# WZ8048C070-V1_1-20230407.net
KiCad netlist of a schematic drawn in EAGLE
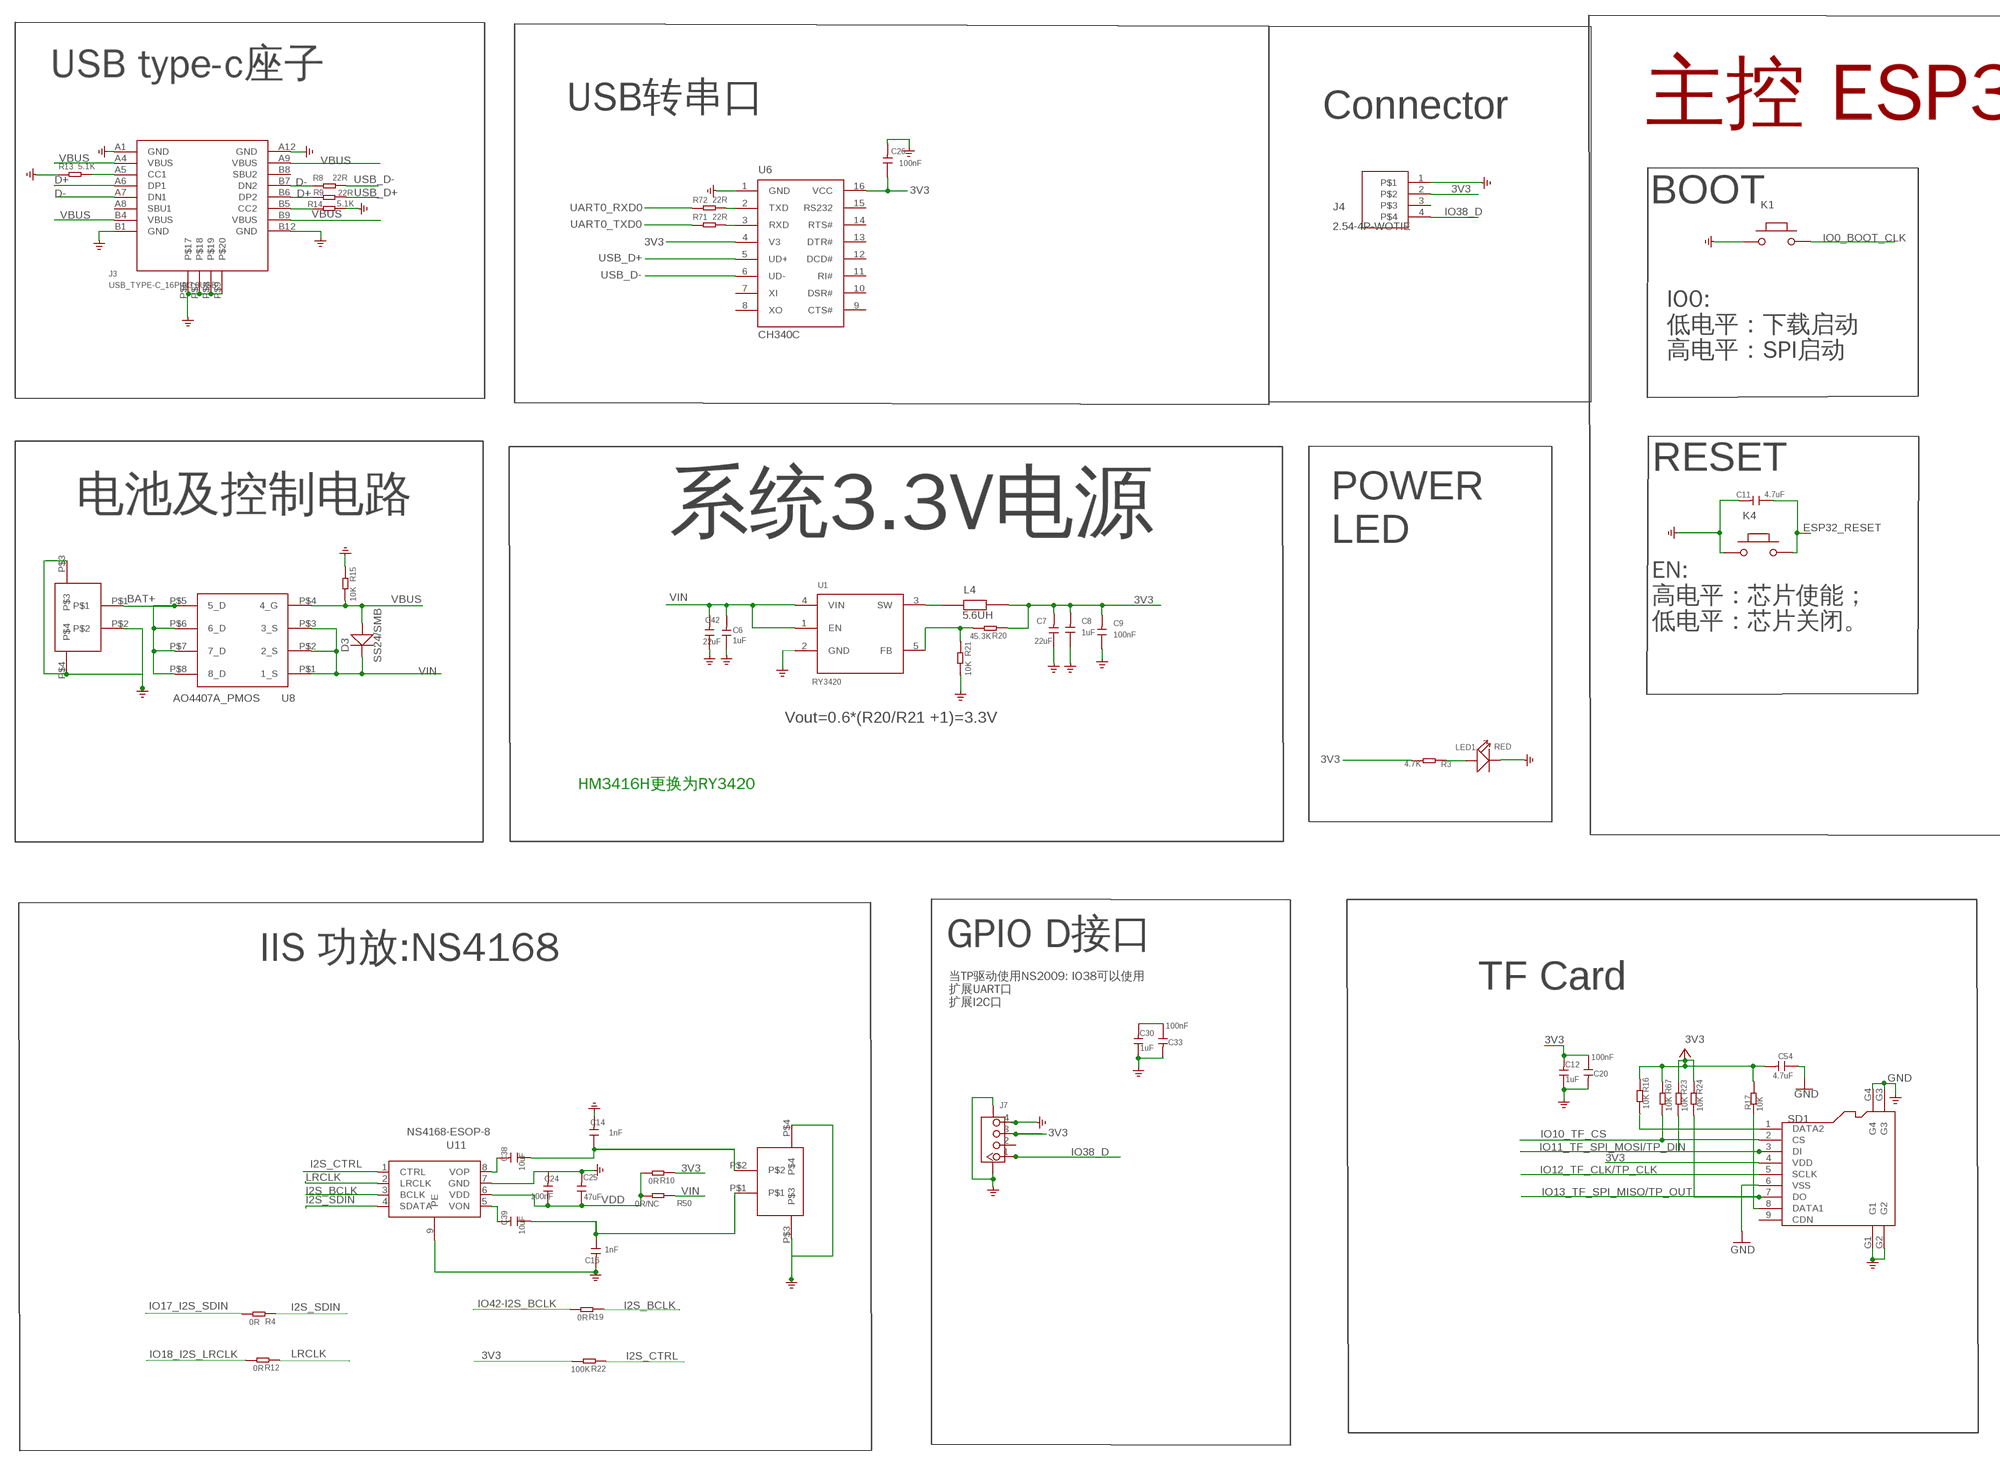
[diagram p0: schematic, sheet 1, part 1 of 2]
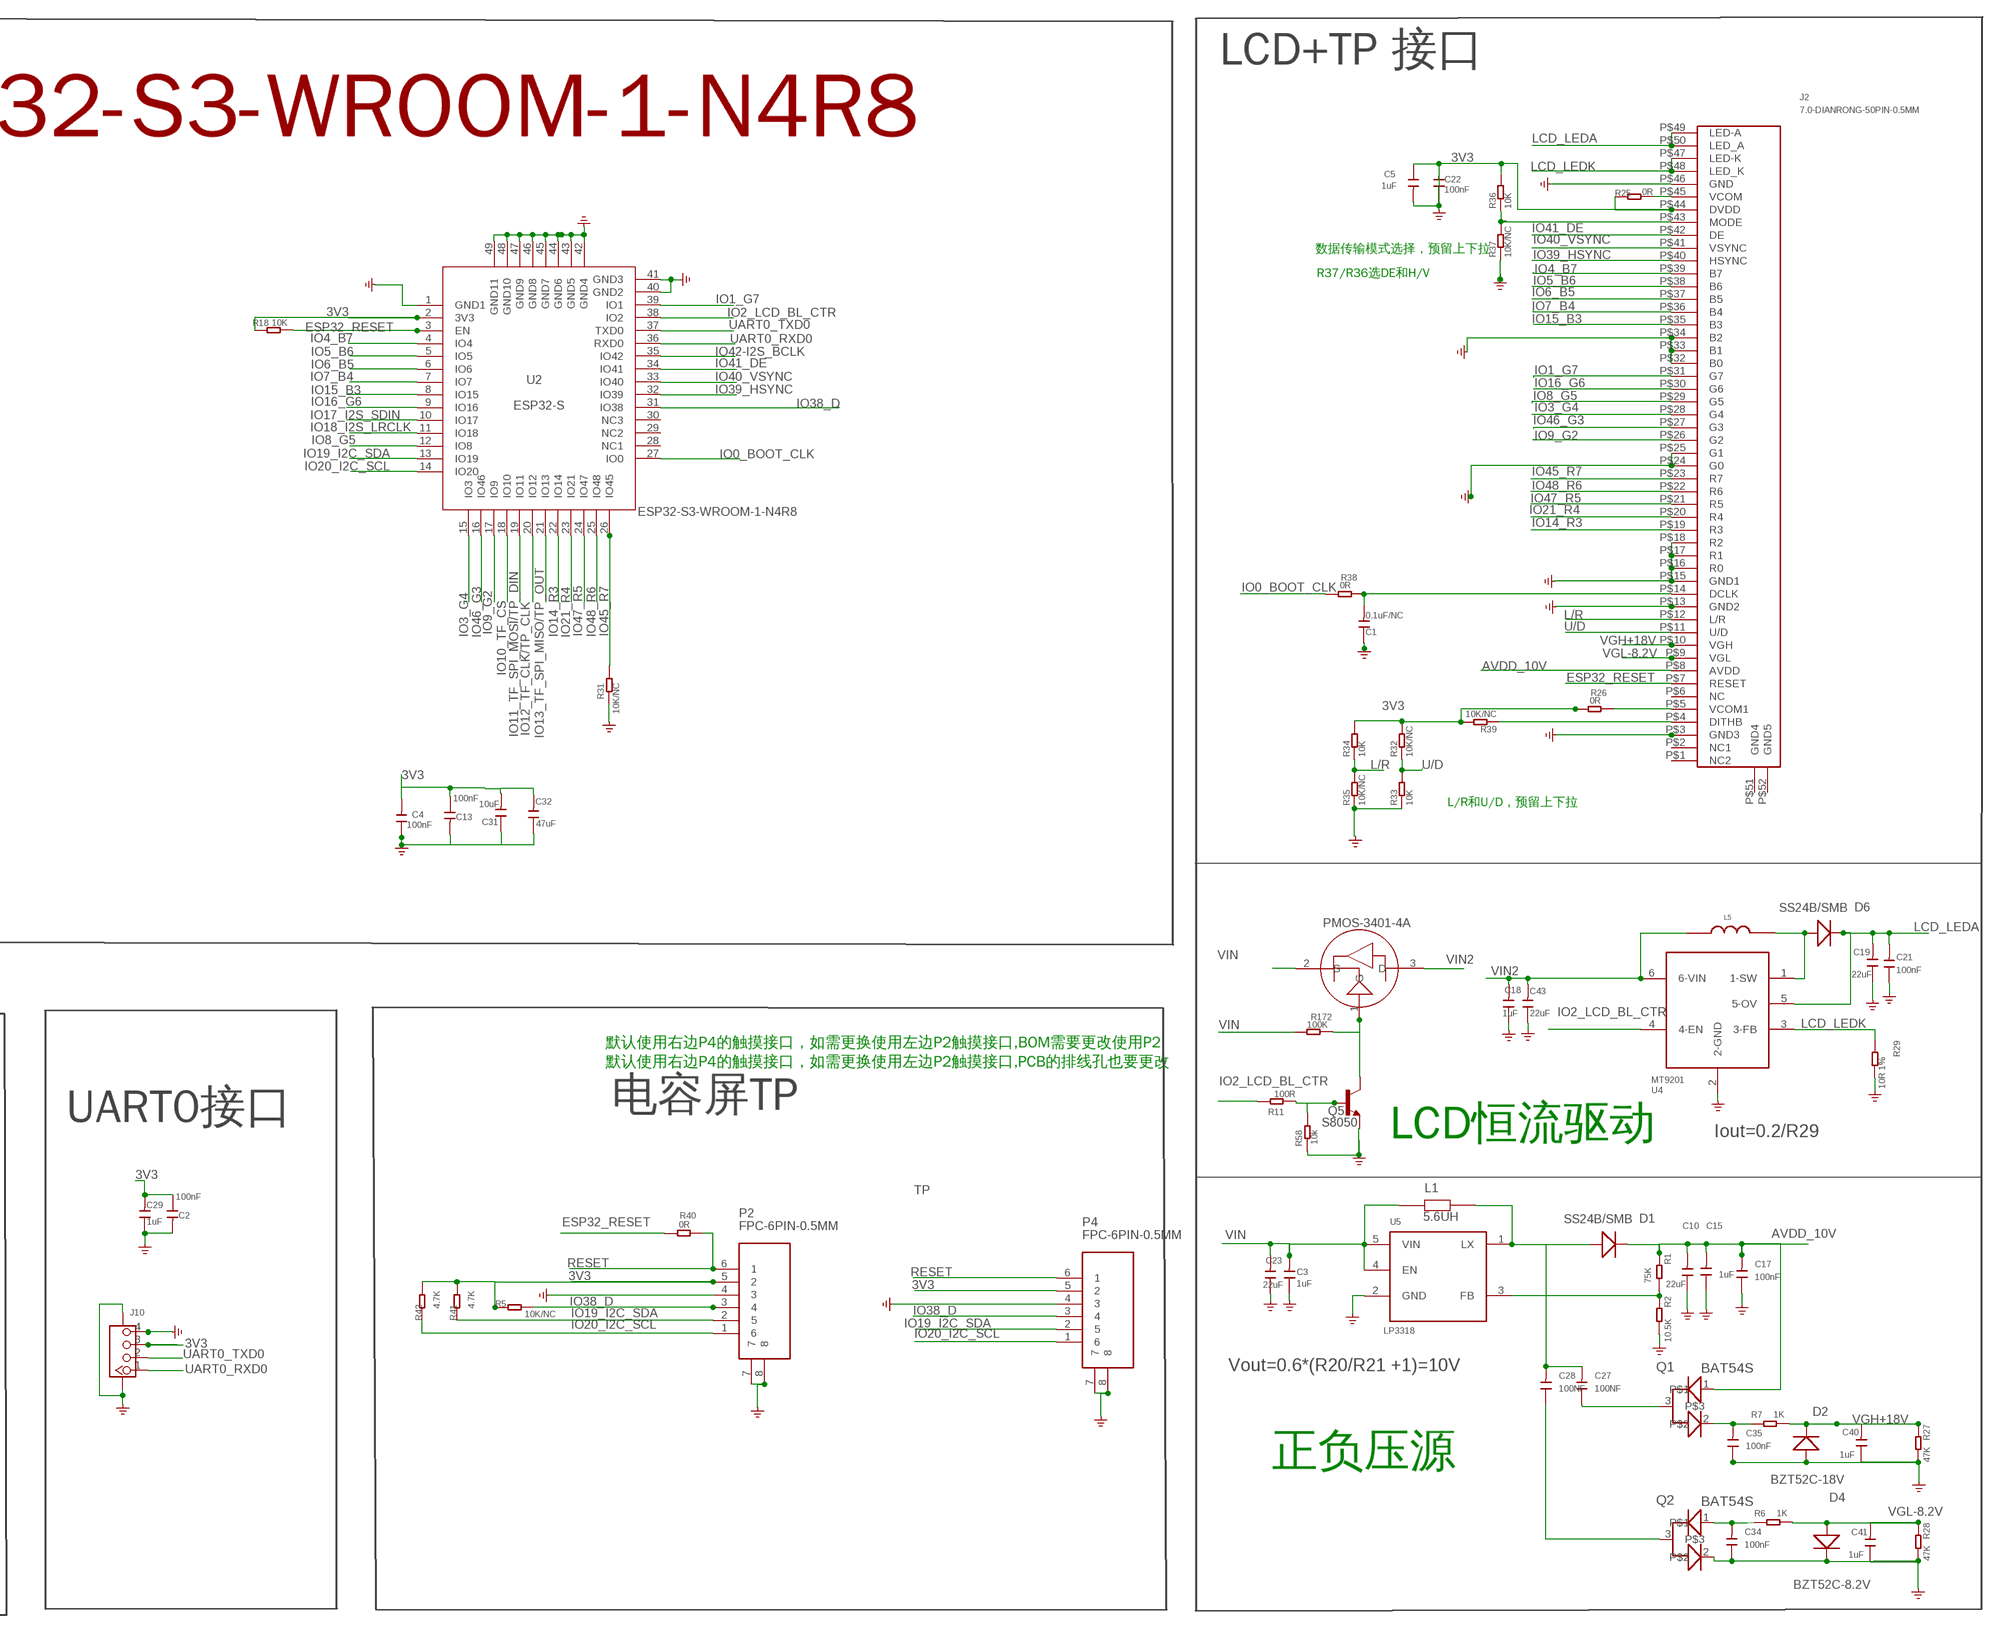
[diagram p1: schematic, sheet 1, part 2 of 2]

(export (version "E")
  (design (tool "Eeschema 10.0.6"))
  (components
    (comp (ref "C1")
      (value "0.1uF/NC")
      (footprint "eagle-import:DISCRETE_C0603")
      (libsource (lib "eagle-import") (part "DISCRETE_C-0603"))
    )
    (comp (ref "C2")
      (value "100nF")
      (footprint "eagle-import:C0603")
      (libsource (lib "eagle-import") (part "C-0603"))
    )
    (comp (ref "C3")
      (value "1uF")
      (footprint "eagle-import:0603")
      (libsource (lib "eagle-import") (part "C0603"))
    )
    (comp (ref "C4")
      (value "100nF")
      (footprint "eagle-import:C0603")
      (libsource (lib "eagle-import") (part "C-0603"))
    )
    (comp (ref "C5")
      (value "1uF")
      (footprint "eagle-import:C0603")
      (libsource (lib "eagle-import") (part "C-0603"))
    )
    (comp (ref "C6")
      (value "1uF")
      (footprint "eagle-import:0603")
      (libsource (lib "eagle-import") (part "C0603"))
    )
    (comp (ref "C7")
      (value "22uF")
      (footprint "eagle-import:0805")
      (libsource (lib "eagle-import") (part "C0805"))
    )
    (comp (ref "C8")
      (value "1uF")
      (footprint "eagle-import:0603")
      (libsource (lib "eagle-import") (part "C0603"))
    )
    (comp (ref "C9")
      (value "100nF")
      (footprint "eagle-import:0603")
      (libsource (lib "eagle-import") (part "C0603"))
    )
    (comp (ref "C10")
      (value "22uF")
      (footprint "eagle-import:0805")
      (libsource (lib "eagle-import") (part "C0805"))
    )
    (comp (ref "C11")
      (value "4.7uF")
      (footprint "eagle-import:0603")
      (libsource (lib "eagle-import") (part "C0603"))
    )
    (comp (ref "C12")
      (value "1uF")
      (footprint "eagle-import:DISCRETE_C0603")
      (libsource (lib "eagle-import") (part "A_xbj_DISCRETE_C-0603"))
    )
    (comp (ref "C13")
      (value "100nF")
      (footprint "eagle-import:C0603")
      (libsource (lib "eagle-import") (part "C-0603"))
    )
    (comp (ref "C14")
      (value "1nF")
      (footprint "eagle-import:C0603")
      (libsource (lib "eagle-import") (part "C-0603"))
    )
    (comp (ref "C15")
      (value "1uF")
      (footprint "eagle-import:0603")
      (libsource (lib "eagle-import") (part "C0603"))
    )
    (comp (ref "C16")
      (value "1nF")
      (footprint "eagle-import:C0603")
      (libsource (lib "eagle-import") (part "C-0603"))
    )
    (comp (ref "C17")
      (value "100nF")
      (footprint "eagle-import:0603")
      (libsource (lib "eagle-import") (part "C0603"))
    )
    (comp (ref "C18")
      (value "1uF")
      (footprint "eagle-import:0603")
      (libsource (lib "eagle-import") (part "C0603"))
    )
    (comp (ref "C19")
      (value "22uF")
      (footprint "eagle-import:0805")
      (libsource (lib "eagle-import") (part "C0805"))
    )
    (comp (ref "C20")
      (value "100nF")
      (footprint "eagle-import:C0603")
      (libsource (lib "eagle-import") (part "C-0603"))
    )
    (comp (ref "C21")
      (value "100nF")
      (footprint "eagle-import:0603")
      (libsource (lib "eagle-import") (part "C0603"))
    )
    (comp (ref "C22")
      (value "100nF")
      (footprint "eagle-import:C0603")
      (libsource (lib "eagle-import") (part "C-0603"))
    )
    (comp (ref "C23")
      (value "22uF")
      (footprint "eagle-import:0805")
      (libsource (lib "eagle-import") (part "C0805"))
    )
    (comp (ref "C24")
      (value "100nF")
      (footprint "eagle-import:C0603")
      (libsource (lib "eagle-import") (part "C-0603"))
    )
    (comp (ref "C25")
      (value "47uF")
      (footprint "eagle-import:0805")
      (libsource (lib "eagle-import") (part "C0805"))
    )
    (comp (ref "C26")
      (value "100nF")
      (footprint "eagle-import:0603")
      (libsource (lib "eagle-import") (part "C0603"))
    )
    (comp (ref "C27")
      (value "100NF")
      (footprint "eagle-import:0603")
      (libsource (lib "eagle-import") (part "C0603"))
    )
    (comp (ref "C28")
      (value "100NF")
      (footprint "eagle-import:0603")
      (libsource (lib "eagle-import") (part "C0603"))
    )
    (comp (ref "C29")
      (value "1uF")
      (footprint "eagle-import:DISCRETE_C0603")
      (libsource (lib "eagle-import") (part "A_xbj_DISCRETE_C-0603"))
    )
    (comp (ref "C30")
      (value "1uF")
      (footprint "eagle-import:DISCRETE_C0603")
      (libsource (lib "eagle-import") (part "A_xbj_DISCRETE_C-0603"))
    )
    (comp (ref "C31")
      (value "10uF")
      (footprint "eagle-import:DISCRETE_C0603")
      (libsource (lib "eagle-import") (part "DISCRETE_C-0603"))
    )
    (comp (ref "C32")
      (value "47uF")
      (footprint "eagle-import:0805")
      (libsource (lib "eagle-import") (part "C0805"))
    )
    (comp (ref "C33")
      (value "100nF")
      (footprint "eagle-import:C0603")
      (libsource (lib "eagle-import") (part "C-0603"))
    )
    (comp (ref "C34")
      (value "100nF")
      (footprint "eagle-import:0603")
      (libsource (lib "eagle-import") (part "C0603"))
    )
    (comp (ref "C35")
      (value "100nF")
      (footprint "eagle-import:0603")
      (libsource (lib "eagle-import") (part "C0603"))
    )
    (comp (ref "C38")
      (value "10uF")
      (footprint "eagle-import:C0603")
      (libsource (lib "eagle-import") (part "C-0603"))
    )
    (comp (ref "C39")
      (value "10uF")
      (footprint "eagle-import:C0603")
      (libsource (lib "eagle-import") (part "C-0603"))
    )
    (comp (ref "C40")
      (value "1uF")
      (footprint "eagle-import:0805")
      (libsource (lib "eagle-import") (part "C0805"))
    )
    (comp (ref "C41")
      (value "1uF")
      (footprint "eagle-import:0805")
      (libsource (lib "eagle-import") (part "C0805"))
    )
    (comp (ref "C42")
      (value "22uF")
      (footprint "eagle-import:0805")
      (libsource (lib "eagle-import") (part "C0805"))
    )
    (comp (ref "C43")
      (value "22uF")
      (footprint "eagle-import:0805")
      (libsource (lib "eagle-import") (part "C0805"))
    )
    (comp (ref "C54")
      (value "4.7uF")
      (footprint "eagle-import:DISCRETE_C0603")
      (libsource (lib "eagle-import") (part "DISCRETE_C-0603"))
    )
    (comp (ref "D1")
      (value "SS24B/SMB")
      (footprint "eagle-import:214AB")
      (libsource (lib "eagle-import") (part "214ABDO-214AB"))
    )
    (comp (ref "D2")
      (value "BZT52C-18V")
      (footprint "eagle-import:DISCRETE_SOD123")
      (libsource (lib "eagle-import") (part "DISCRETE_D1206"))
    )
    (comp (ref "D3")
      (value "SS24/SMB")
      (footprint "eagle-import:214AB")
      (libsource (lib "eagle-import") (part "214ABDO-214AB"))
    )
    (comp (ref "D4")
      (value "BZT52C-8.2V")
      (footprint "eagle-import:DISCRETE_SOD123")
      (libsource (lib "eagle-import") (part "DISCRETE_D1206"))
    )
    (comp (ref "D6")
      (value "SS24B/SMB")
      (footprint "eagle-import:214AB")
      (libsource (lib "eagle-import") (part "214ABDO-214AB"))
    )
    (comp (ref "J1")
      (value "PH2.0WT-2PIN")
      (footprint "eagle-import:PH2.0WT-2PIN")
      (libsource (lib "eagle-import") (part "PH2.0WT-2PIN"))
    )
    (comp (ref "J2")
      (value "7.0-DIANRONG-50PIN-0.5MM")
      (footprint "eagle-import:7.0-DAINRONG-50PIN-0.5MM")
      (libsource (lib "eagle-import") (part "7.0-DIANRONG-50PIN-0.5MM"))
    )
    (comp (ref "J3")
      (value "USB_TYPE-C_16PIN3.0USB")
      (footprint "eagle-import:KEVIN_3.0TYPEC-SMD")
      (libsource (lib "eagle-import") (part "USB_TYPE-C_16PIN3.0USB"))
    )
    (comp (ref "J4")
      (value "2.54-4P-WOTIE")
      (footprint "eagle-import:2.54-4P-WOTIE")
      (libsource (lib "eagle-import") (part "2.54-4P-WOTIE"))
    )
    (comp (ref "J5")
      (value "PH2.0WT-2PIN")
      (footprint "eagle-import:PH2.0WT-2PIN")
      (libsource (lib "eagle-import") (part "PH2.0WT-2PIN"))
    )
    (comp (ref "J7")
      (value "CONNECTOR_TWIG-4P-2.0-SMD-FEMALE-REINFORCE90D")
      (footprint "eagle-import:CONNECTOR_4P-SMD-2.0-90D")
      (libsource (lib "eagle-import") (part "CONNECTOR_TWIG-4P-2.0-SMD-FEMALE-REINFORCE90D"))
    )
    (comp (ref "J10")
      (value "CONNECTOR_TWIG-4P-2.0-SMD-FEMALE-REINFORCE90D")
      (footprint "eagle-import:CONNECTOR_4P-SMD-2.0-90D")
      (libsource (lib "eagle-import") (part "CONNECTOR_TWIG-4P-2.0-SMD-FEMALE-REINFORCE90D"))
    )
    (comp (ref "K1")
      (value "BUTTON")
      (footprint "eagle-import:157SW")
      (libsource (lib "eagle-import") (part "PB157"))
    )
    (comp (ref "K4")
      (value "BUTTON")
      (footprint "eagle-import:157SW")
      (libsource (lib "eagle-import") (part "PB157"))
    )
    (comp (ref "L1")
      (value "5.6UH")
      (footprint "eagle-import:CD54")
      (libsource (lib "eagle-import") (part "CROWPI2-MB-V1.4-20211012_CMP201209UD1R0MT"))
    )
    (comp (ref "L4")
      (value "5.6UH")
      (footprint "eagle-import:CD54")
      (libsource (lib "eagle-import") (part "CROWPI2-MB-V1.4-20211012_CMP201209UD1R0MT"))
    )
    (comp (ref "L5")
      (value "CD32_6.8uH")
      (footprint "eagle-import:CD32")
      (libsource (lib "eagle-import") (part "CD32_950MA"))
    )
    (comp (ref "LED1")
      (value "RED")
      (footprint "eagle-import:DISCRETE_LED-0603")
      (libsource (lib "eagle-import") (part "DISCRETE_LED0603"))
    )
    (comp (ref "P2")
      (value "FPC-6PIN-0.5MM")
      (footprint "eagle-import:FPC-6PIN-0.5MM")
      (libsource (lib "eagle-import") (part "FPC-6PIN-0.5MM"))
    )
    (comp (ref "P4")
      (value "FPC-6PIN-0.5MM")
      (footprint "eagle-import:FPC-6PIN-0.5MM")
      (libsource (lib "eagle-import") (part "FPC-6PIN-0.5MM"))
    )
    (comp (ref "Q1")
      (value "BAT54S")
      (footprint "eagle-import:SOT23-3")
      (libsource (lib "eagle-import") (part "BAT54S"))
    )
    (comp (ref "Q2")
      (value "BAT54S")
      (footprint "eagle-import:SOT23-3")
      (libsource (lib "eagle-import") (part "BAT54S"))
    )
    (comp (ref "Q5")
      (value "S8050")
      (footprint "eagle-import:SPARKFUN_SOT23")
      (libsource (lib "eagle-import") (part "SPARKFUN_TRANSISTOR_NPNSOT23"))
    )
    (comp (ref "Q30")
      (value "PMOS-3401-4A")
      (footprint "eagle-import:SOT-23")
      (libsource (lib "eagle-import") (part "P-MOS-SOT23"))
    )
    (comp (ref "R1")
      (value "75K")
      (footprint "eagle-import:DISCRETE_R0603")
      (libsource (lib "eagle-import") (part "Crowtail-_LED-V2.0-20190615-01_DISCRETE_R-0603"))
    )
    (comp (ref "R2")
      (value "10.5K")
      (footprint "eagle-import:DISCRETE_R0603")
      (libsource (lib "eagle-import") (part "Crowtail-_LED-V2.0-20190615-01_DISCRETE_R-0603"))
    )
    (comp (ref "R3")
      (value "4.7K")
      (footprint "eagle-import:DISCRETE_R0603")
      (libsource (lib "eagle-import") (part "Crowtail-_LED-V2.0-20190615-01_DISCRETE_R-0603"))
    )
    (comp (ref "R4")
      (value "0R")
      (footprint "eagle-import:DISCRETE_R0603")
      (libsource (lib "eagle-import") (part "Crowtail-_LED-V2.0-20190615-01_DISCRETE_R-0603"))
    )
    (comp (ref "R5")
      (value "10K/NC")
      (footprint "eagle-import:DISCRETE_R0603")
      (libsource (lib "eagle-import") (part "Crowtail-_LED-V2.0-20190615-01_DISCRETE_R-0603"))
    )
    (comp (ref "R6")
      (value "1K")
      (footprint "eagle-import:DISCRETE_R0603")
      (libsource (lib "eagle-import") (part "Crowtail-_LED-V2.0-20190615-01_DISCRETE_R-0603"))
    )
    (comp (ref "R7")
      (value "1K")
      (footprint "eagle-import:DISCRETE_R0603")
      (libsource (lib "eagle-import") (part "Crowtail-_LED-V2.0-20190615-01_DISCRETE_R-0603"))
    )
    (comp (ref "R8")
      (value "22R")
      (footprint "eagle-import:DISCRETE_R0603")
      (libsource (lib "eagle-import") (part "Crowtail-_LED-V2.0-20190615-01_DISCRETE_R-0603"))
    )
    (comp (ref "R9")
      (value "22R")
      (footprint "eagle-import:DISCRETE_R0603")
      (libsource (lib "eagle-import") (part "Crowtail-_LED-V2.0-20190615-01_DISCRETE_R-0603"))
    )
    (comp (ref "R10")
      (value "0R")
      (footprint "eagle-import:DISCRETE_R0603")
      (libsource (lib "eagle-import") (part "Crowtail-_LED-V2.0-20190615-01_DISCRETE_R-0603"))
    )
    (comp (ref "R11")
      (value "100R")
      (footprint "eagle-import:R0603")
      (libsource (lib "eagle-import") (part "R0603"))
    )
    (comp (ref "R12")
      (value "0R")
      (footprint "eagle-import:DISCRETE_R0603")
      (libsource (lib "eagle-import") (part "Crowtail-_LED-V2.0-20190615-01_DISCRETE_R-0603"))
    )
    (comp (ref "R13")
      (value "5.1K")
      (footprint "eagle-import:DISCRETE_R0603")
      (libsource (lib "eagle-import") (part "Crowtail-_LED-V2.0-20190615-01_DISCRETE_R-0603"))
    )
    (comp (ref "R14")
      (value "5.1K")
      (footprint "eagle-import:DISCRETE_R0603")
      (libsource (lib "eagle-import") (part "Crowtail-_LED-V2.0-20190615-01_DISCRETE_R-0603"))
    )
    (comp (ref "R15")
      (value "10K")
      (footprint "eagle-import:DISCRETE_R0603")
      (libsource (lib "eagle-import") (part "Crowtail-_LED-V2.0-20190615-01_DISCRETE_R-0603"))
    )
    (comp (ref "R16")
      (value "10K")
      (footprint "eagle-import:DISCRETE_R0603")
      (libsource (lib "eagle-import") (part "Crowtail-_LED-V2.0-20190615-01_DISCRETE_R-0603"))
    )
    (comp (ref "R17")
      (value "10K")
      (footprint "eagle-import:DISCRETE_R0603")
      (libsource (lib "eagle-import") (part "Crowtail-_LED-V2.0-20190615-01_DISCRETE_R-0603"))
    )
    (comp (ref "R18")
      (value "10K")
      (footprint "eagle-import:DISCRETE_R0603")
      (libsource (lib "eagle-import") (part "Crowtail-_LED-V2.0-20190615-01_DISCRETE_R-0603"))
    )
    (comp (ref "R19")
      (value "0R")
      (footprint "eagle-import:DISCRETE_R0603")
      (libsource (lib "eagle-import") (part "Crowtail-_LED-V2.0-20190615-01_DISCRETE_R-0603"))
    )
    (comp (ref "R20")
      (value "45.3K")
      (footprint "eagle-import:DISCRETE_R0603")
      (libsource (lib "eagle-import") (part "Crowtail-_LED-V2.0-20190615-01_DISCRETE_R-0603"))
    )
    (comp (ref "R21")
      (value "10K")
      (footprint "eagle-import:DISCRETE_R0603")
      (libsource (lib "eagle-import") (part "Crowtail-_LED-V2.0-20190615-01_DISCRETE_R-0603"))
    )
    (comp (ref "R22")
      (value "100K")
      (footprint "eagle-import:DISCRETE_R0603")
      (libsource (lib "eagle-import") (part "Crowtail-_LED-V2.0-20190615-01_DISCRETE_R-0603"))
    )
    (comp (ref "R23")
      (value "10K")
      (footprint "eagle-import:DISCRETE_R0603")
      (libsource (lib "eagle-import") (part "Crowtail-_LED-V2.0-20190615-01_DISCRETE_R-0603"))
    )
    (comp (ref "R24")
      (value "10K")
      (footprint "eagle-import:DISCRETE_R0603")
      (libsource (lib "eagle-import") (part "Crowtail-_LED-V2.0-20190615-01_DISCRETE_R-0603"))
    )
    (comp (ref "R25")
      (value "0R")
      (footprint "eagle-import:DISCRETE_R0603")
      (libsource (lib "eagle-import") (part "Crowtail-_LED-V2.0-20190615-01_DISCRETE_R-0603"))
    )
    (comp (ref "R26")
      (value "0R")
      (footprint "eagle-import:R0603")
      (libsource (lib "eagle-import") (part "R-0603"))
    )
    (comp (ref "R27")
      (value "47K")
      (footprint "eagle-import:DISCRETE_R0603")
      (libsource (lib "eagle-import") (part "Crowtail-_LED-V2.0-20190615-01_DISCRETE_R-0603"))
    )
    (comp (ref "R28")
      (value "47K")
      (footprint "eagle-import:DISCRETE_R0603")
      (libsource (lib "eagle-import") (part "Crowtail-_LED-V2.0-20190615-01_DISCRETE_R-0603"))
    )
    (comp (ref "R29")
      (value "10R 1%")
      (footprint "eagle-import:DISCRETE_R0603")
      (libsource (lib "eagle-import") (part "Crowtail-_LED-V2.0-20190615-01_DISCRETE_R-0603"))
    )
    (comp (ref "R31")
      (value "10K/NC")
      (footprint "eagle-import:R0603")
      (libsource (lib "eagle-import") (part "R0603"))
    )
    (comp (ref "R32")
      (value "10K/NC")
      (footprint "eagle-import:DISCRETE_R0603")
      (libsource (lib "eagle-import") (part "DISCRETE_R-0603"))
    )
    (comp (ref "R33")
      (value "10K")
      (footprint "eagle-import:DISCRETE_R0603")
      (libsource (lib "eagle-import") (part "DISCRETE_R-0603"))
    )
    (comp (ref "R34")
      (value "10K")
      (footprint "eagle-import:DISCRETE_R0603")
      (libsource (lib "eagle-import") (part "DISCRETE_R-0603"))
    )
    (comp (ref "R35")
      (value "10K/NC")
      (footprint "eagle-import:DISCRETE_R0603")
      (libsource (lib "eagle-import") (part "DISCRETE_R-0603"))
    )
    (comp (ref "R36")
      (value "10K")
      (footprint "eagle-import:DISCRETE_R0603")
      (libsource (lib "eagle-import") (part "DISCRETE_R-0603"))
    )
    (comp (ref "R37")
      (value "10K/NC")
      (footprint "eagle-import:DISCRETE_R0603")
      (libsource (lib "eagle-import") (part "DISCRETE_R-0603"))
    )
    (comp (ref "R38")
      (value "0R")
      (footprint "eagle-import:R0603")
      (libsource (lib "eagle-import") (part "R-0603"))
    )
    (comp (ref "R39")
      (value "10K/NC")
      (footprint "eagle-import:DISCRETE_R0603")
      (libsource (lib "eagle-import") (part "DISCRETE_R-0603"))
    )
    (comp (ref "R40")
      (value "0R")
      (footprint "eagle-import:R0603")
      (libsource (lib "eagle-import") (part "R-0603"))
    )
    (comp (ref "R41")
      (value "4.7K")
      (footprint "eagle-import:DISCRETE_R0603")
      (libsource (lib "eagle-import") (part "Crowtail-_LED-V2.0-20190615-01_DISCRETE_R-0603"))
    )
    (comp (ref "R42")
      (value "4.7K")
      (footprint "eagle-import:DISCRETE_R0603")
      (libsource (lib "eagle-import") (part "Crowtail-_LED-V2.0-20190615-01_DISCRETE_R-0603"))
    )
    (comp (ref "R50")
      (value "0R/NC")
      (footprint "eagle-import:DISCRETE_R0603")
      (libsource (lib "eagle-import") (part "Crowtail-_LED-V2.0-20190615-01_DISCRETE_R-0603"))
    )
    (comp (ref "R58")
      (value "10k")
      (footprint "eagle-import:R0603")
      (libsource (lib "eagle-import") (part "R0603"))
    )
    (comp (ref "R67")
      (value "10K")
      (footprint "eagle-import:DISCRETE_R0603")
      (libsource (lib "eagle-import") (part "Crowtail-_LED-V2.0-20190615-01_DISCRETE_R-0603"))
    )
    (comp (ref "R71")
      (value "22R")
      (footprint "eagle-import:DISCRETE_R0603")
      (libsource (lib "eagle-import") (part "Crowtail-_LED-V2.0-20190615-01_DISCRETE_R-0603"))
    )
    (comp (ref "R72")
      (value "22R")
      (footprint "eagle-import:DISCRETE_R0603")
      (libsource (lib "eagle-import") (part "Crowtail-_LED-V2.0-20190615-01_DISCRETE_R-0603"))
    )
    (comp (ref "R172")
      (value "100K")
      (footprint "eagle-import:R0603")
      (libsource (lib "eagle-import") (part "R-0603"))
    )
    (comp (ref "SD1")
      (value "HOLDER-MICROSD-9P")
      (footprint "eagle-import:9P-SMD-W_-RING")
      (libsource (lib "eagle-import") (part "HOLDER-MICROSD-9P"))
    )
    (comp (ref "U1")
      (value "RY3420")
      (footprint "eagle-import:A_XBJ_SOT23-5")
      (libsource (lib "eagle-import") (part "A_XBJ_HM3420B"))
    )
    (comp (ref "U2")
      (value "ESP32-S")
      (footprint "eagle-import:ESP32-S3")
      (fields (field (name "U2") "ESP32-S3-WROOM-1-N4R8"))
      (libsource (lib "eagle-import") (part "ESP32-S"))
    )
    (comp (ref "U4")
      (value "MT9201")
      (footprint "eagle-import:SOT23-6")
      (libsource (lib "eagle-import") (part "MT9201"))
    )
    (comp (ref "U5")
      (value "LP3318")
      (footprint "eagle-import:LP3318_SOT23-5")
      (libsource (lib "eagle-import") (part "LP3318"))
    )
    (comp (ref "U6")
      (value "CH340C")
      (footprint "eagle-import:SOP-16")
      (libsource (lib "eagle-import") (part "CH340G"))
    )
    (comp (ref "U8")
      (value "AO4407A_PMOS")
      (footprint "eagle-import:SOP8")
      (libsource (lib "eagle-import") (part "T_PMOS_AO4407A_SOP8"))
    )
    (comp (ref "U11")
      (value "NS4168-ESOP-8")
      (footprint "eagle-import:NS4168-ESOP-8")
      (libsource (lib "eagle-import") (part "NS4168-ESOP-8"))
    )
  )
  (nets
    (net (code "1") (name "+3V3") (class "Default")
      (node (ref "C12") (pin "2") (pinfunction "2_2") (pintype "passive"))
      (node (ref "C13") (pin "1") (pinfunction "1_1") (pintype "passive"))
      (node (ref "C2") (pin "1") (pinfunction "1_1") (pintype "passive"))
      (node (ref "C20") (pin "1") (pinfunction "1_1") (pintype "passive"))
      (node (ref "C22") (pin "2") (pinfunction "2_2") (pintype "passive"))
      (node (ref "C26") (pin "1") (pinfunction "1_1") (pintype "passive"))
      (node (ref "C29") (pin "2") (pinfunction "2_2") (pintype "passive"))
      (node (ref "C30") (pin "2") (pinfunction "2_2") (pintype "passive"))
      (node (ref "C31") (pin "2") (pinfunction "2_2") (pintype "passive"))
      (node (ref "C32") (pin "2") (pinfunction "2_2") (pintype "passive"))
      (node (ref "C33") (pin "1") (pinfunction "1_1") (pintype "passive"))
      (node (ref "C4") (pin "2") (pinfunction "2_2") (pintype "passive"))
      (node (ref "C5") (pin "1") (pinfunction "1_1") (pintype "passive"))
      (node (ref "C54") (pin "2") (pinfunction "2_2") (pintype "passive"))
      (node (ref "C7") (pin "2") (pinfunction "2_2") (pintype "passive"))
      (node (ref "C8") (pin "2") (pinfunction "2_2") (pintype "passive"))
      (node (ref "C9") (pin "2") (pinfunction "2_2") (pintype "passive"))
      (node (ref "J10") (pin "3") (pinfunction "3_3") (pintype "bidirectional"))
      (node (ref "J2") (pin "P$44") (pinfunction "DVDD_P$44") (pintype "bidirectional"))
      (node (ref "J4") (pin "2") (pinfunction "P$2_2") (pintype "bidirectional"))
      (node (ref "J7") (pin "3") (pinfunction "3_3") (pintype "bidirectional"))
      (node (ref "L4") (pin "2") (pinfunction "2_2") (pintype "bidirectional"))
      (node (ref "P2") (pin "5") (pinfunction "2_5") (pintype "bidirectional"))
      (node (ref "P4") (pin "5") (pinfunction "2_5") (pintype "bidirectional"))
      (node (ref "R10") (pin "1") (pinfunction "1_1") (pintype "passive"))
      (node (ref "R16") (pin "1") (pinfunction "1_1") (pintype "passive"))
      (node (ref "R17") (pin "1") (pinfunction "1_1") (pintype "passive"))
      (node (ref "R18") (pin "1") (pinfunction "1_1") (pintype "passive"))
      (node (ref "R20") (pin "1") (pinfunction "1_1") (pintype "passive"))
      (node (ref "R22") (pin "2") (pinfunction "2_2") (pintype "passive"))
      (node (ref "R23") (pin "1") (pinfunction "1_1") (pintype "passive"))
      (node (ref "R24") (pin "1") (pinfunction "1_1") (pintype "passive"))
      (node (ref "R25") (pin "1") (pinfunction "1_1") (pintype "passive"))
      (node (ref "R26") (pin "1") (pinfunction "1_1") (pintype "passive"))
      (node (ref "R3") (pin "2") (pinfunction "2_2") (pintype "passive"))
      (node (ref "R32") (pin "2") (pinfunction "2_2") (pintype "passive"))
      (node (ref "R34") (pin "2") (pinfunction "2_2") (pintype "passive"))
      (node (ref "R36") (pin "2") (pinfunction "2_2") (pintype "passive"))
      (node (ref "R39") (pin "2") (pinfunction "2_2") (pintype "passive"))
      (node (ref "R41") (pin "2") (pinfunction "2_2") (pintype "passive"))
      (node (ref "R42") (pin "2") (pinfunction "2_2") (pintype "passive"))
      (node (ref "R5") (pin "1") (pinfunction "1_1") (pintype "passive"))
      (node (ref "R67") (pin "1") (pinfunction "1_1") (pintype "passive"))
      (node (ref "SD1") (pin "4") (pinfunction "VDD_4") (pintype "bidirectional"))
      (node (ref "U2") (pin "2") (pinfunction "3V3_2") (pintype "bidirectional"))
      (node (ref "U6") (pin "16") (pinfunction "VCC_16") (pintype "bidirectional"))
      (node (ref "U6") (pin "4") (pinfunction "V3_4") (pintype "bidirectional"))
    )
    (net (code "2") (name "/AVDD_10V") (class "Default")
      (node (ref "C10") (pin "2") (pinfunction "2_2") (pintype "passive"))
      (node (ref "C15") (pin "2") (pinfunction "2_2") (pintype "passive"))
      (node (ref "C17") (pin "2") (pinfunction "2_2") (pintype "passive"))
      (node (ref "D1") (pin "2") (pinfunction "-_2") (pintype "passive"))
      (node (ref "J2") (pin "P$8") (pinfunction "AVDD_P$8") (pintype "bidirectional"))
      (node (ref "Q1") (pin "1") (pinfunction "P$1_1") (pintype "bidirectional"))
      (node (ref "R1") (pin "1") (pinfunction "1_1") (pintype "passive"))
    )
    (net (code "3") (name "/BAT+") (class "Default")
      (node (ref "J1") (pin "P$1") (pinfunction "P$1_P$1") (pintype "bidirectional"))
      (node (ref "U8") (pin "P$5") (pinfunction "5_D_P$5") (pintype "bidirectional"))
      (node (ref "U8") (pin "P$6") (pinfunction "6_D_P$6") (pintype "bidirectional"))
      (node (ref "U8") (pin "P$7") (pinfunction "7_D_P$7") (pintype "bidirectional"))
      (node (ref "U8") (pin "P$8") (pinfunction "8_D_P$8") (pintype "bidirectional"))
    )
    (net (code "4") (name "/D+") (class "Default")
      (node (ref "J3") (pin "A6") (pinfunction "DP1_A6") (pintype "bidirectional"))
      (node (ref "J3") (pin "B6") (pinfunction "DP2_B6") (pintype "bidirectional"))
      (node (ref "R9") (pin "1") (pinfunction "1_1") (pintype "passive"))
    )
    (net (code "5") (name "/D-") (class "Default")
      (node (ref "J3") (pin "A7") (pinfunction "DN1_A7") (pintype "bidirectional"))
      (node (ref "J3") (pin "B7") (pinfunction "DN2_B7") (pintype "bidirectional"))
      (node (ref "R8") (pin "1") (pinfunction "1_1") (pintype "passive"))
    )
    (net (code "6") (name "/ESP32_RESET") (class "Default")
      (node (ref "C11") (pin "1") (pinfunction "1_1") (pintype "passive"))
      (node (ref "J2") (pin "P$7") (pinfunction "RESET_P$7") (pintype "bidirectional"))
      (node (ref "K4") (pin "2") (pinfunction "2_2") (pintype "passive"))
      (node (ref "R18") (pin "2") (pinfunction "2_2") (pintype "passive"))
      (node (ref "R40") (pin "1") (pinfunction "1_1") (pintype "passive"))
      (node (ref "U2") (pin "3") (pinfunction "EN_3") (pintype "bidirectional"))
    )
    (net (code "7") (name "/I2S_BCLK") (class "Default")
      (node (ref "R19") (pin "1") (pinfunction "1_1") (pintype "passive"))
      (node (ref "U11") (pin "3") (pinfunction "BCLK_3") (pintype "bidirectional"))
    )
    (net (code "8") (name "/I2S_CTRL") (class "Default")
      (node (ref "R22") (pin "1") (pinfunction "1_1") (pintype "passive"))
      (node (ref "U11") (pin "1") (pinfunction "CTRL_1") (pintype "bidirectional"))
    )
    (net (code "9") (name "/I2S_SDIN") (class "Default")
      (node (ref "R4") (pin "1") (pinfunction "1_1") (pintype "passive"))
      (node (ref "U11") (pin "4") (pinfunction "SDATA_4") (pintype "bidirectional"))
    )
    (net (code "10") (name "/IO0_BOOT_CLK") (class "Default")
      (node (ref "K1") (pin "2") (pinfunction "2_2") (pintype "passive"))
      (node (ref "R38") (pin "1") (pinfunction "1_1") (pintype "passive"))
      (node (ref "U2") (pin "27") (pinfunction "IO0_27") (pintype "bidirectional"))
    )
    (net (code "11") (name "/IO1_G7") (class "Default")
      (node (ref "J2") (pin "P$31") (pinfunction "G7_P$31") (pintype "bidirectional"))
      (node (ref "U2") (pin "39") (pinfunction "IO1_39") (pintype "bidirectional"))
    )
    (net (code "12") (name "/IO2_LCD_BL_CTR") (class "Default")
      (node (ref "R11") (pin "2") (pinfunction "2_2") (pintype "passive"))
      (node (ref "U2") (pin "38") (pinfunction "IO2_38") (pintype "bidirectional"))
      (node (ref "U4") (pin "4") (pinfunction "4-EN_4") (pintype "bidirectional"))
    )
    (net (code "13") (name "/IO3_G4") (class "Default")
      (node (ref "J2") (pin "P$28") (pinfunction "G4_P$28") (pintype "bidirectional"))
      (node (ref "U2") (pin "15") (pinfunction "IO3_15") (pintype "bidirectional"))
    )
    (net (code "14") (name "/IO4_B7") (class "Default")
      (node (ref "J2") (pin "P$39") (pinfunction "B7_P$39") (pintype "bidirectional"))
      (node (ref "U2") (pin "4") (pinfunction "IO4_4") (pintype "bidirectional"))
    )
    (net (code "15") (name "/IO5_B6") (class "Default")
      (node (ref "J2") (pin "P$38") (pinfunction "B6_P$38") (pintype "bidirectional"))
      (node (ref "U2") (pin "5") (pinfunction "IO5_5") (pintype "bidirectional"))
    )
    (net (code "16") (name "/IO6_B5") (class "Default")
      (node (ref "J2") (pin "P$37") (pinfunction "B5_P$37") (pintype "bidirectional"))
      (node (ref "U2") (pin "6") (pinfunction "IO6_6") (pintype "bidirectional"))
    )
    (net (code "17") (name "/IO7_B4") (class "Default")
      (node (ref "J2") (pin "P$36") (pinfunction "B4_P$36") (pintype "bidirectional"))
      (node (ref "U2") (pin "7") (pinfunction "IO7_7") (pintype "bidirectional"))
    )
    (net (code "18") (name "/IO8_G5") (class "Default")
      (node (ref "J2") (pin "P$29") (pinfunction "G5_P$29") (pintype "bidirectional"))
      (node (ref "U2") (pin "12") (pinfunction "IO8_12") (pintype "bidirectional"))
    )
    (net (code "19") (name "/IO9_G2") (class "Default")
      (node (ref "J2") (pin "P$26") (pinfunction "G2_P$26") (pintype "bidirectional"))
      (node (ref "U2") (pin "17") (pinfunction "IO9_17") (pintype "bidirectional"))
    )
    (net (code "20") (name "/IO10_TF_CS") (class "Default")
      (node (ref "R67") (pin "2") (pinfunction "2_2") (pintype "passive"))
      (node (ref "SD1") (pin "2") (pinfunction "CS_2") (pintype "bidirectional"))
      (node (ref "U2") (pin "18") (pinfunction "IO10_18") (pintype "bidirectional"))
    )
    (net (code "21") (name "/IO11_TF_SPI_MOSI{slash}TP_DIN") (class "Default")
      (node (ref "R23") (pin "2") (pinfunction "2_2") (pintype "passive"))
      (node (ref "SD1") (pin "3") (pinfunction "DI_3") (pintype "bidirectional"))
      (node (ref "U2") (pin "19") (pinfunction "IO11_19") (pintype "bidirectional"))
    )
    (net (code "22") (name "/IO12_TF_CLK{slash}TP_CLK") (class "Default")
      (node (ref "SD1") (pin "5") (pinfunction "SCLK_5") (pintype "bidirectional"))
      (node (ref "U2") (pin "20") (pinfunction "IO12_20") (pintype "bidirectional"))
    )
    (net (code "23") (name "/IO13_TF_SPI_MISO{slash}TP_OUT") (class "Default")
      (node (ref "R24") (pin "2") (pinfunction "2_2") (pintype "passive"))
      (node (ref "SD1") (pin "7") (pinfunction "DO_7") (pintype "bidirectional"))
      (node (ref "U2") (pin "21") (pinfunction "IO13_21") (pintype "bidirectional"))
    )
    (net (code "24") (name "/IO14_R3") (class "Default")
      (node (ref "J2") (pin "P$19") (pinfunction "R3_P$19") (pintype "bidirectional"))
      (node (ref "U2") (pin "22") (pinfunction "IO14_22") (pintype "bidirectional"))
    )
    (net (code "25") (name "/IO15_B3") (class "Default")
      (node (ref "J2") (pin "P$35") (pinfunction "B3_P$35") (pintype "bidirectional"))
      (node (ref "U2") (pin "8") (pinfunction "IO15_8") (pintype "bidirectional"))
    )
    (net (code "26") (name "/IO16_G6") (class "Default")
      (node (ref "J2") (pin "P$30") (pinfunction "G6_P$30") (pintype "bidirectional"))
      (node (ref "U2") (pin "9") (pinfunction "IO16_9") (pintype "bidirectional"))
    )
    (net (code "27") (name "/IO17_I2S_SDIN") (class "Default")
      (node (ref "R4") (pin "2") (pinfunction "2_2") (pintype "passive"))
      (node (ref "U2") (pin "10") (pinfunction "IO17_10") (pintype "bidirectional"))
    )
    (net (code "28") (name "/IO18_I2S_LRCLK") (class "Default")
      (node (ref "R12") (pin "2") (pinfunction "2_2") (pintype "passive"))
      (node (ref "U2") (pin "11") (pinfunction "IO18_11") (pintype "bidirectional"))
    )
    (net (code "29") (name "/IO19_I2C_SDA") (class "Default")
      (node (ref "P2") (pin "2") (pinfunction "5_2") (pintype "bidirectional"))
      (node (ref "P4") (pin "2") (pinfunction "5_2") (pintype "bidirectional"))
      (node (ref "R41") (pin "1") (pinfunction "1_1") (pintype "passive"))
      (node (ref "U2") (pin "13") (pinfunction "IO19_13") (pintype "bidirectional"))
    )
    (net (code "30") (name "/IO20_I2C_SCL") (class "Default")
      (node (ref "P2") (pin "1") (pinfunction "6_1") (pintype "bidirectional"))
      (node (ref "P4") (pin "1") (pinfunction "6_1") (pintype "bidirectional"))
      (node (ref "R42") (pin "1") (pinfunction "1_1") (pintype "passive"))
      (node (ref "U2") (pin "14") (pinfunction "IO20_14") (pintype "bidirectional"))
    )
    (net (code "31") (name "/IO21_R4") (class "Default")
      (node (ref "J2") (pin "P$20") (pinfunction "R4_P$20") (pintype "bidirectional"))
      (node (ref "U2") (pin "23") (pinfunction "IO21_23") (pintype "bidirectional"))
    )
    (net (code "32") (name "/IO38_D") (class "Default")
      (node (ref "J4") (pin "4") (pinfunction "P$4_4") (pintype "bidirectional"))
      (node (ref "J7") (pin "1") (pinfunction "1_1") (pintype "bidirectional"))
      (node (ref "P2") (pin "3") (pinfunction "4_3") (pintype "bidirectional"))
      (node (ref "P4") (pin "3") (pinfunction "4_3") (pintype "bidirectional"))
      (node (ref "R5") (pin "2") (pinfunction "2_2") (pintype "passive"))
      (node (ref "U2") (pin "31") (pinfunction "IO38_31") (pintype "bidirectional"))
    )
    (net (code "33") (name "/IO39_HSYNC") (class "Default")
      (node (ref "J2") (pin "P$40") (pinfunction "HSYNC_P$40") (pintype "bidirectional"))
      (node (ref "U2") (pin "32") (pinfunction "IO39_32") (pintype "bidirectional"))
    )
    (net (code "34") (name "/IO40_VSYNC") (class "Default")
      (node (ref "J2") (pin "P$41") (pinfunction "VSYNC_P$41") (pintype "bidirectional"))
      (node (ref "U2") (pin "33") (pinfunction "IO40_33") (pintype "bidirectional"))
    )
    (net (code "35") (name "/IO41_DE") (class "Default")
      (node (ref "J2") (pin "P$42") (pinfunction "DE_P$42") (pintype "bidirectional"))
      (node (ref "U2") (pin "34") (pinfunction "IO41_34") (pintype "bidirectional"))
    )
    (net (code "36") (name "/IO42-I2S_BCLK") (class "Default")
      (node (ref "R19") (pin "2") (pinfunction "2_2") (pintype "passive"))
      (node (ref "U2") (pin "35") (pinfunction "IO42_35") (pintype "bidirectional"))
    )
    (net (code "37") (name "/IO45_R7") (class "Default")
      (node (ref "J2") (pin "P$23") (pinfunction "R7_P$23") (pintype "bidirectional"))
      (node (ref "R31") (pin "2") (pinfunction "2_2") (pintype "passive"))
      (node (ref "U2") (pin "26") (pinfunction "IO45_26") (pintype "bidirectional"))
    )
    (net (code "38") (name "/IO46_G3") (class "Default")
      (node (ref "J2") (pin "P$27") (pinfunction "G3_P$27") (pintype "bidirectional"))
      (node (ref "U2") (pin "16") (pinfunction "IO46_16") (pintype "bidirectional"))
    )
    (net (code "39") (name "/IO47_R5") (class "Default")
      (node (ref "J2") (pin "P$21") (pinfunction "R5_P$21") (pintype "bidirectional"))
      (node (ref "U2") (pin "24") (pinfunction "IO47_24") (pintype "bidirectional"))
    )
    (net (code "40") (name "/IO48_R6") (class "Default")
      (node (ref "J2") (pin "P$22") (pinfunction "R6_P$22") (pintype "bidirectional"))
      (node (ref "U2") (pin "25") (pinfunction "IO48_25") (pintype "bidirectional"))
    )
    (net (code "41") (name "/LCD_LEDA") (class "Default")
      (node (ref "C19") (pin "2") (pinfunction "2_2") (pintype "passive"))
      (node (ref "C21") (pin "2") (pinfunction "2_2") (pintype "passive"))
      (node (ref "D6") (pin "2") (pinfunction "-_2") (pintype "passive"))
      (node (ref "J2") (pin "P$49") (pinfunction "LED-A_P$49") (pintype "bidirectional"))
      (node (ref "J2") (pin "P$50") (pinfunction "LED_A_P$50") (pintype "bidirectional"))
      (node (ref "U4") (pin "5") (pinfunction "5-OV_5") (pintype "bidirectional"))
    )
    (net (code "42") (name "/LCD_LEDK") (class "Default")
      (node (ref "J2") (pin "P$47") (pinfunction "LED-K_P$47") (pintype "bidirectional"))
      (node (ref "J2") (pin "P$48") (pinfunction "LED_K_P$48") (pintype "bidirectional"))
      (node (ref "R29") (pin "1") (pinfunction "1_1") (pintype "passive"))
      (node (ref "U4") (pin "3") (pinfunction "3-FB_3") (pintype "bidirectional"))
    )
    (net (code "43") (name "/LRCLK") (class "Default")
      (node (ref "R12") (pin "1") (pinfunction "1_1") (pintype "passive"))
      (node (ref "U11") (pin "2") (pinfunction "LRCLK_2") (pintype "bidirectional"))
    )
    (net (code "44") (name "/L{slash}R") (class "Default")
      (node (ref "J2") (pin "P$12") (pinfunction "L/R_P$12") (pintype "bidirectional"))
      (node (ref "R34") (pin "1") (pinfunction "1_1") (pintype "passive"))
      (node (ref "R35") (pin "2") (pinfunction "2_2") (pintype "passive"))
    )
    (net (code "45") (name "/RESET") (class "Default")
      (node (ref "P2") (pin "6") (pinfunction "1_6") (pintype "bidirectional"))
      (node (ref "P4") (pin "6") (pinfunction "1_6") (pintype "bidirectional"))
      (node (ref "R40") (pin "2") (pinfunction "2_2") (pintype "passive"))
    )
    (net (code "46") (name "/UART0_RXD0") (class "Default")
      (node (ref "J10") (pin "1") (pinfunction "1_1") (pintype "bidirectional"))
      (node (ref "R72") (pin "1") (pinfunction "1_1") (pintype "passive"))
      (node (ref "U2") (pin "36") (pinfunction "RXD0_36") (pintype "bidirectional"))
    )
    (net (code "47") (name "/UART0_TXD0") (class "Default")
      (node (ref "J10") (pin "2") (pinfunction "2_2") (pintype "bidirectional"))
      (node (ref "R71") (pin "1") (pinfunction "1_1") (pintype "passive"))
      (node (ref "U2") (pin "37") (pinfunction "TXD0_37") (pintype "bidirectional"))
    )
    (net (code "48") (name "/USB_D+") (class "Default")
      (node (ref "R9") (pin "2") (pinfunction "2_2") (pintype "passive"))
      (node (ref "U6") (pin "5") (pinfunction "UD+_5") (pintype "bidirectional"))
    )
    (net (code "49") (name "/USB_D-") (class "Default")
      (node (ref "R8") (pin "2") (pinfunction "2_2") (pintype "passive"))
      (node (ref "U6") (pin "6") (pinfunction "UD-_6") (pintype "bidirectional"))
    )
    (net (code "50") (name "/U{slash}D") (class "Default")
      (node (ref "J2") (pin "P$11") (pinfunction "U/D_P$11") (pintype "bidirectional"))
      (node (ref "R32") (pin "1") (pinfunction "1_1") (pintype "passive"))
      (node (ref "R33") (pin "2") (pinfunction "2_2") (pintype "passive"))
    )
    (net (code "51") (name "/VBUS") (class "Default")
      (node (ref "D3") (pin "1") (pinfunction "+_1") (pintype "passive"))
      (node (ref "J3") (pin "A4") (pinfunction "VBUS_A4") (pintype "bidirectional"))
      (node (ref "J3") (pin "A9") (pinfunction "VBUS_A9") (pintype "bidirectional"))
      (node (ref "J3") (pin "B4") (pinfunction "VBUS_B4") (pintype "bidirectional"))
      (node (ref "J3") (pin "B9") (pinfunction "VBUS_B9") (pintype "bidirectional"))
      (node (ref "R15") (pin "2") (pinfunction "2_2") (pintype "passive"))
      (node (ref "U8") (pin "P$4") (pinfunction "4_G_P$4") (pintype "bidirectional"))
    )
    (net (code "52") (name "/VDD") (class "Default")
      (node (ref "C24") (pin "1") (pinfunction "1_1") (pintype "passive"))
      (node (ref "C25") (pin "1") (pinfunction "1_1") (pintype "passive"))
      (node (ref "R10") (pin "2") (pinfunction "2_2") (pintype "passive"))
      (node (ref "R50") (pin "2") (pinfunction "2_2") (pintype "passive"))
      (node (ref "U11") (pin "6") (pinfunction "VDD_6") (pintype "bidirectional"))
    )
    (net (code "53") (name "/VGH+18V") (class "Default")
      (node (ref "C40") (pin "2") (pinfunction "2_2") (pintype "passive"))
      (node (ref "D2") (pin "-") (pinfunction "-_-") (pintype "passive"))
      (node (ref "J2") (pin "P$10") (pinfunction "VGH_P$10") (pintype "bidirectional"))
      (node (ref "R27") (pin "1") (pinfunction "1_1") (pintype "passive"))
      (node (ref "R7") (pin "2") (pinfunction "2_2") (pintype "passive"))
    )
    (net (code "54") (name "/VGL-8.2V") (class "Default")
      (node (ref "C41") (pin "2") (pinfunction "2_2") (pintype "passive"))
      (node (ref "D4") (pin "+") (pinfunction "+_+") (pintype "passive"))
      (node (ref "J2") (pin "P$9") (pinfunction "VGL_P$9") (pintype "bidirectional"))
      (node (ref "R28") (pin "1") (pinfunction "1_1") (pintype "passive"))
      (node (ref "R6") (pin "2") (pinfunction "2_2") (pintype "passive"))
    )
    (net (code "55") (name "/VIN") (class "Default")
      (node (ref "C23") (pin "2") (pinfunction "2_2") (pintype "passive"))
      (node (ref "C3") (pin "2") (pinfunction "2_2") (pintype "passive"))
      (node (ref "C42") (pin "2") (pinfunction "2_2") (pintype "passive"))
      (node (ref "C6") (pin "2") (pinfunction "2_2") (pintype "passive"))
      (node (ref "D3") (pin "2") (pinfunction "-_2") (pintype "passive"))
      (node (ref "L1") (pin "1") (pinfunction "1_1") (pintype "bidirectional"))
      (node (ref "Q30") (pin "2") (pinfunction "S_2") (pintype "bidirectional"))
      (node (ref "R172") (pin "1") (pinfunction "1_1") (pintype "passive"))
      (node (ref "R50") (pin "1") (pinfunction "1_1") (pintype "passive"))
      (node (ref "U1") (pin "1") (pinfunction "EN_1") (pintype "bidirectional"))
      (node (ref "U1") (pin "4") (pinfunction "VIN_4") (pintype "bidirectional"))
      (node (ref "U5") (pin "4") (pinfunction "EN_4") (pintype "bidirectional"))
      (node (ref "U5") (pin "5") (pinfunction "VIN_5") (pintype "bidirectional"))
      (node (ref "U8") (pin "P$1") (pinfunction "1_S_P$1") (pintype "bidirectional"))
      (node (ref "U8") (pin "P$2") (pinfunction "2_S_P$2") (pintype "bidirectional"))
      (node (ref "U8") (pin "P$3") (pinfunction "3_S_P$3") (pintype "bidirectional"))
    )
    (net (code "56") (name "/VIN2") (class "Default")
      (node (ref "C18") (pin "2") (pinfunction "2_2") (pintype "passive"))
      (node (ref "C43") (pin "2") (pinfunction "2_2") (pintype "passive"))
      (node (ref "L5") (pin "1") (pinfunction "1_1") (pintype "bidirectional"))
      (node (ref "Q30") (pin "3") (pinfunction "D_3") (pintype "bidirectional"))
      (node (ref "U4") (pin "6") (pinfunction "6-VIN_6") (pintype "bidirectional"))
    )
    (net (code "57") (name "GND") (class "Default")
      (node (ref "C1") (pin "1") (pinfunction "1_1") (pintype "passive"))
      (node (ref "C10") (pin "1") (pinfunction "1_1") (pintype "passive"))
      (node (ref "C11") (pin "2") (pinfunction "2_2") (pintype "passive"))
      (node (ref "C12") (pin "1") (pinfunction "1_1") (pintype "passive"))
      (node (ref "C13") (pin "2") (pinfunction "2_2") (pintype "passive"))
      (node (ref "C14") (pin "2") (pinfunction "2_2") (pintype "passive"))
      (node (ref "C15") (pin "1") (pinfunction "1_1") (pintype "passive"))
      (node (ref "C16") (pin "2") (pinfunction "2_2") (pintype "passive"))
      (node (ref "C17") (pin "1") (pinfunction "1_1") (pintype "passive"))
      (node (ref "C18") (pin "1") (pinfunction "1_1") (pintype "passive"))
      (node (ref "C19") (pin "1") (pinfunction "1_1") (pintype "passive"))
      (node (ref "C2") (pin "2") (pinfunction "2_2") (pintype "passive"))
      (node (ref "C20") (pin "2") (pinfunction "2_2") (pintype "passive"))
      (node (ref "C21") (pin "1") (pinfunction "1_1") (pintype "passive"))
      (node (ref "C22") (pin "1") (pinfunction "1_1") (pintype "passive"))
      (node (ref "C23") (pin "1") (pinfunction "1_1") (pintype "passive"))
      (node (ref "C24") (pin "2") (pinfunction "2_2") (pintype "passive"))
      (node (ref "C25") (pin "2") (pinfunction "2_2") (pintype "passive"))
      (node (ref "C26") (pin "2") (pinfunction "2_2") (pintype "passive"))
      (node (ref "C29") (pin "1") (pinfunction "1_1") (pintype "passive"))
      (node (ref "C3") (pin "1") (pinfunction "1_1") (pintype "passive"))
      (node (ref "C30") (pin "1") (pinfunction "1_1") (pintype "passive"))
      (node (ref "C31") (pin "1") (pinfunction "1_1") (pintype "passive"))
      (node (ref "C32") (pin "1") (pinfunction "1_1") (pintype "passive"))
      (node (ref "C33") (pin "2") (pinfunction "2_2") (pintype "passive"))
      (node (ref "C34") (pin "1") (pinfunction "1_1") (pintype "passive"))
      (node (ref "C35") (pin "1") (pinfunction "1_1") (pintype "passive"))
      (node (ref "C4") (pin "1") (pinfunction "1_1") (pintype "passive"))
      (node (ref "C40") (pin "1") (pinfunction "1_1") (pintype "passive"))
      (node (ref "C41") (pin "1") (pinfunction "1_1") (pintype "passive"))
      (node (ref "C42") (pin "1") (pinfunction "1_1") (pintype "passive"))
      (node (ref "C43") (pin "1") (pinfunction "1_1") (pintype "passive"))
      (node (ref "C5") (pin "2") (pinfunction "2_2") (pintype "passive"))
      (node (ref "C54") (pin "1") (pinfunction "1_1") (pintype "passive"))
      (node (ref "C6") (pin "1") (pinfunction "1_1") (pintype "passive"))
      (node (ref "C7") (pin "1") (pinfunction "1_1") (pintype "passive"))
      (node (ref "C8") (pin "1") (pinfunction "1_1") (pintype "passive"))
      (node (ref "C9") (pin "1") (pinfunction "1_1") (pintype "passive"))
      (node (ref "D2") (pin "+") (pinfunction "+_+") (pintype "passive"))
      (node (ref "D4") (pin "-") (pinfunction "-_-") (pintype "passive"))
      (node (ref "J1") (pin "P$2") (pinfunction "P$2_P$2") (pintype "bidirectional"))
      (node (ref "J1") (pin "P$3") (pinfunction "P$3_P$3") (pintype "bidirectional"))
      (node (ref "J1") (pin "P$4") (pinfunction "P$4_P$4") (pintype "bidirectional"))
      (node (ref "J10") (pin "4") (pinfunction "4_4") (pintype "bidirectional"))
      (node (ref "J10") (pin "SS1") (pinfunction "SS1_SS1") (pintype "bidirectional"))
      (node (ref "J10") (pin "SS2") (pinfunction "SS2_SS2") (pintype "bidirectional"))
      (node (ref "J2") (pin "P$13") (pinfunction "GND2_P$13") (pintype "bidirectional"))
      (node (ref "J2") (pin "P$15") (pinfunction "GND1_P$15") (pintype "bidirectional"))
      (node (ref "J2") (pin "P$16") (pinfunction "R0_P$16") (pintype "bidirectional"))
      (node (ref "J2") (pin "P$17") (pinfunction "R1_P$17") (pintype "bidirectional"))
      (node (ref "J2") (pin "P$18") (pinfunction "R2_P$18") (pintype "bidirectional"))
      (node (ref "J2") (pin "P$24") (pinfunction "G0_P$24") (pintype "bidirectional"))
      (node (ref "J2") (pin "P$25") (pinfunction "G1_P$25") (pintype "bidirectional"))
      (node (ref "J2") (pin "P$3") (pinfunction "GND3_P$3") (pintype "bidirectional"))
      (node (ref "J2") (pin "P$32") (pinfunction "B0_P$32") (pintype "bidirectional"))
      (node (ref "J2") (pin "P$33") (pinfunction "B1_P$33") (pintype "bidirectional"))
      (node (ref "J2") (pin "P$34") (pinfunction "B2_P$34") (pintype "bidirectional"))
      (node (ref "J2") (pin "P$46") (pinfunction "GND_P$46") (pintype "bidirectional"))
      (node (ref "J3") (pin "A1") (pinfunction "GND_A1") (pintype "bidirectional"))
      (node (ref "J3") (pin "A12") (pinfunction "GND_A12") (pintype "bidirectional"))
      (node (ref "J3") (pin "B1") (pinfunction "GND_B1") (pintype "bidirectional"))
      (node (ref "J3") (pin "B12") (pinfunction "GND_B12") (pintype "bidirectional"))
      (node (ref "J3") (pin "P$6") (pinfunction "P$17_P$6") (pintype "bidirectional"))
      (node (ref "J3") (pin "P$7") (pinfunction "P$18_P$7") (pintype "bidirectional"))
      (node (ref "J3") (pin "P$8") (pinfunction "P$19_P$8") (pintype "bidirectional"))
      (node (ref "J3") (pin "P$9") (pinfunction "P$20_P$9") (pintype "bidirectional"))
      (node (ref "J4") (pin "1") (pinfunction "P$1_1") (pintype "bidirectional"))
      (node (ref "J5") (pin "P$3") (pinfunction "P$3_P$3") (pintype "bidirectional"))
      (node (ref "J5") (pin "P$4") (pinfunction "P$4_P$4") (pintype "bidirectional"))
      (node (ref "J7") (pin "4") (pinfunction "4_4") (pintype "bidirectional"))
      (node (ref "J7") (pin "SS1") (pinfunction "SS1_SS1") (pintype "bidirectional"))
      (node (ref "J7") (pin "SS2") (pinfunction "SS2_SS2") (pintype "bidirectional"))
      (node (ref "K1") (pin "1") (pinfunction "1_1") (pintype "passive"))
      (node (ref "K4") (pin "1") (pinfunction "1_1") (pintype "passive"))
      (node (ref "LED1") (pin "-") (pinfunction "-_-") (pintype "passive"))
      (node (ref "P2") (pin "4") (pinfunction "3_4") (pintype "bidirectional"))
      (node (ref "P2") (pin "7") (pinfunction "7_7") (pintype "bidirectional"))
      (node (ref "P2") (pin "8") (pinfunction "8_8") (pintype "bidirectional"))
      (node (ref "P4") (pin "4") (pinfunction "3_4") (pintype "bidirectional"))
      (node (ref "P4") (pin "7") (pinfunction "7_7") (pintype "bidirectional"))
      (node (ref "P4") (pin "8") (pinfunction "8_8") (pintype "bidirectional"))
      (node (ref "Q2") (pin "2") (pinfunction "P$2_2") (pintype "bidirectional"))
      (node (ref "Q5") (pin "2") (pinfunction "E_2") (pintype "passive"))
      (node (ref "R13") (pin "1") (pinfunction "1_1") (pintype "passive"))
      (node (ref "R14") (pin "2") (pinfunction "2_2") (pintype "passive"))
      (node (ref "R15") (pin "1") (pinfunction "1_1") (pintype "passive"))
      (node (ref "R2") (pin "2") (pinfunction "2_2") (pintype "passive"))
      (node (ref "R21") (pin "2") (pinfunction "2_2") (pintype "passive"))
      (node (ref "R27") (pin "2") (pinfunction "2_2") (pintype "passive"))
      (node (ref "R28") (pin "2") (pinfunction "2_2") (pintype "passive"))
      (node (ref "R29") (pin "2") (pinfunction "2_2") (pintype "passive"))
      (node (ref "R31") (pin "1") (pinfunction "1_1") (pintype "passive"))
      (node (ref "R33") (pin "1") (pinfunction "1_1") (pintype "passive"))
      (node (ref "R35") (pin "1") (pinfunction "1_1") (pintype "passive"))
      (node (ref "R37") (pin "1") (pinfunction "1_1") (pintype "passive"))
      (node (ref "R58") (pin "1") (pinfunction "1_1") (pintype "passive"))
      (node (ref "SD1") (pin "6") (pinfunction "VSS_6") (pintype "bidirectional"))
      (node (ref "SD1") (pin "G1") (pinfunction "G1_G1") (pintype "bidirectional"))
      (node (ref "SD1") (pin "G2") (pinfunction "G2_G2") (pintype "bidirectional"))
      (node (ref "SD1") (pin "G3") (pinfunction "G3_G3") (pintype "bidirectional"))
      (node (ref "SD1") (pin "G4") (pinfunction "G4_G4") (pintype "bidirectional"))
      (node (ref "U1") (pin "2") (pinfunction "GND_2") (pintype "bidirectional"))
      (node (ref "U11") (pin "7") (pinfunction "GND_7") (pintype "bidirectional"))
      (node (ref "U11") (pin "9") (pinfunction "PE_9") (pintype "bidirectional"))
      (node (ref "U2") (pin "1") (pinfunction "GND1_1") (pintype "bidirectional"))
      (node (ref "U2") (pin "40") (pinfunction "GND2_40") (pintype "bidirectional"))
      (node (ref "U2") (pin "41") (pinfunction "GND3_41") (pintype "bidirectional"))
      (node (ref "U2") (pin "42") (pinfunction "GND4_42") (pintype "bidirectional"))
      (node (ref "U2") (pin "43") (pinfunction "GND5_43") (pintype "bidirectional"))
      (node (ref "U2") (pin "44") (pinfunction "GND6_44") (pintype "bidirectional"))
      (node (ref "U2") (pin "45") (pinfunction "GND7_45") (pintype "bidirectional"))
      (node (ref "U2") (pin "46") (pinfunction "GND8_46") (pintype "bidirectional"))
      (node (ref "U2") (pin "47") (pinfunction "GND9_47") (pintype "bidirectional"))
      (node (ref "U2") (pin "48") (pinfunction "GND10_48") (pintype "bidirectional"))
      (node (ref "U2") (pin "49") (pinfunction "GND11_49") (pintype "bidirectional"))
      (node (ref "U4") (pin "2") (pinfunction "2-GND_2") (pintype "bidirectional"))
      (node (ref "U5") (pin "2") (pinfunction "GND_2") (pintype "bidirectional"))
      (node (ref "U6") (pin "1") (pinfunction "GND_1") (pintype "bidirectional"))
    )
    (net (code "58") (name "Net-(C14-Pad1)") (class "Default")
      (node (ref "C14") (pin "1") (pinfunction "1_1") (pintype "passive"))
      (node (ref "C38") (pin "1") (pinfunction "1_1") (pintype "passive"))
      (node (ref "J5") (pin "P$2") (pinfunction "P$2_P$2") (pintype "bidirectional"))
    )
    (net (code "59") (name "Net-(C16-Pad1)") (class "Default")
      (node (ref "C16") (pin "1") (pinfunction "1_1") (pintype "passive"))
      (node (ref "C39") (pin "1") (pinfunction "1_1") (pintype "passive"))
      (node (ref "J5") (pin "P$1") (pinfunction "P$1_P$1") (pintype "bidirectional"))
    )
    (net (code "60") (name "Net-(D1-+)") (class "Default")
      (node (ref "C27") (pin "2") (pinfunction "2_2") (pintype "passive"))
      (node (ref "C28") (pin "2") (pinfunction "2_2") (pintype "passive"))
      (node (ref "D1") (pin "1") (pinfunction "+_1") (pintype "passive"))
      (node (ref "L1") (pin "2") (pinfunction "2_2") (pintype "bidirectional"))
      (node (ref "U5") (pin "1") (pinfunction "LX_1") (pintype "bidirectional"))
    )
    (net (code "61") (name "Net-(D6-+)") (class "Default")
      (node (ref "D6") (pin "1") (pinfunction "+_1") (pintype "passive"))
      (node (ref "L5") (pin "2") (pinfunction "2_2") (pintype "bidirectional"))
      (node (ref "U4") (pin "1") (pinfunction "1-SW_1") (pintype "bidirectional"))
    )
    (net (code "62") (name "Net-(J2-DCLK)") (class "Default")
      (node (ref "C1") (pin "2") (pinfunction "2_2") (pintype "passive"))
      (node (ref "J2") (pin "P$14") (pinfunction "DCLK_P$14") (pintype "bidirectional"))
      (node (ref "R38") (pin "2") (pinfunction "2_2") (pintype "passive"))
    )
    (net (code "63") (name "Net-(J2-DITHB)") (class "Default")
      (node (ref "J2") (pin "P$4") (pinfunction "DITHB_P$4") (pintype "bidirectional"))
      (node (ref "R39") (pin "1") (pinfunction "1_1") (pintype "passive"))
    )
    (net (code "64") (name "Net-(J2-MODE)") (class "Default")
      (node (ref "J2") (pin "P$43") (pinfunction "MODE_P$43") (pintype "bidirectional"))
      (node (ref "R36") (pin "1") (pinfunction "1_1") (pintype "passive"))
      (node (ref "R37") (pin "2") (pinfunction "2_2") (pintype "passive"))
    )
    (net (code "65") (name "Net-(J2-VCOM)") (class "Default")
      (node (ref "J2") (pin "P$45") (pinfunction "VCOM_P$45") (pintype "bidirectional"))
      (node (ref "R25") (pin "2") (pinfunction "2_2") (pintype "passive"))
    )
    (net (code "66") (name "Net-(J2-VCOM1)") (class "Default")
      (node (ref "J2") (pin "P$5") (pinfunction "VCOM1_P$5") (pintype "bidirectional"))
      (node (ref "R26") (pin "2") (pinfunction "2_2") (pintype "passive"))
    )
    (net (code "67") (name "Net-(J3-CC1)") (class "Default")
      (node (ref "J3") (pin "A5") (pinfunction "CC1_A5") (pintype "bidirectional"))
      (node (ref "R13") (pin "2") (pinfunction "2_2") (pintype "passive"))
    )
    (net (code "68") (name "Net-(J3-CC2)") (class "Default")
      (node (ref "J3") (pin "B5") (pinfunction "CC2_B5") (pintype "bidirectional"))
      (node (ref "R14") (pin "1") (pinfunction "1_1") (pintype "passive"))
    )
    (net (code "69") (name "Net-(LED1-Pad+)") (class "Default")
      (node (ref "LED1") (pin "+") (pinfunction "+_+") (pintype "passive"))
      (node (ref "R3") (pin "1") (pinfunction "1_1") (pintype "passive"))
    )
    (net (code "70") (name "Net-(Q1-P$2)") (class "Default")
      (node (ref "C35") (pin "2") (pinfunction "2_2") (pintype "passive"))
      (node (ref "Q1") (pin "2") (pinfunction "P$2_2") (pintype "bidirectional"))
      (node (ref "R7") (pin "1") (pinfunction "1_1") (pintype "passive"))
    )
    (net (code "71") (name "Net-(Q1-P$3)") (class "Default")
      (node (ref "C27") (pin "1") (pinfunction "1_1") (pintype "passive"))
      (node (ref "Q1") (pin "3") (pinfunction "P$3_3") (pintype "bidirectional"))
    )
    (net (code "72") (name "Net-(Q2-P$1)") (class "Default")
      (node (ref "C34") (pin "2") (pinfunction "2_2") (pintype "passive"))
      (node (ref "Q2") (pin "1") (pinfunction "P$1_1") (pintype "bidirectional"))
      (node (ref "R6") (pin "1") (pinfunction "1_1") (pintype "passive"))
    )
    (net (code "73") (name "Net-(Q2-P$3)") (class "Default")
      (node (ref "C28") (pin "1") (pinfunction "1_1") (pintype "passive"))
      (node (ref "Q2") (pin "3") (pinfunction "P$3_3") (pintype "bidirectional"))
    )
    (net (code "74") (name "Net-(Q5-B)") (class "Default")
      (node (ref "Q5") (pin "1") (pinfunction "B_1") (pintype "passive"))
      (node (ref "R11") (pin "1") (pinfunction "1_1") (pintype "passive"))
      (node (ref "R58") (pin "2") (pinfunction "2_2") (pintype "passive"))
    )
    (net (code "75") (name "Net-(Q30-G)") (class "Default")
      (node (ref "Q30") (pin "1") (pinfunction "G_1") (pintype "bidirectional"))
      (node (ref "Q5") (pin "3") (pinfunction "C_3") (pintype "passive"))
      (node (ref "R172") (pin "2") (pinfunction "2_2") (pintype "passive"))
    )
    (net (code "76") (name "Net-(SD1-DATA1)") (class "Default")
      (node (ref "R17") (pin "2") (pinfunction "2_2") (pintype "passive"))
      (node (ref "SD1") (pin "8") (pinfunction "DATA1_8") (pintype "bidirectional"))
    )
    (net (code "77") (name "Net-(SD1-DATA2)") (class "Default")
      (node (ref "R16") (pin "2") (pinfunction "2_2") (pintype "passive"))
      (node (ref "SD1") (pin "1") (pinfunction "DATA2_1") (pintype "bidirectional"))
    )
    (net (code "78") (name "Net-(U1-FB)") (class "Default")
      (node (ref "R20") (pin "2") (pinfunction "2_2") (pintype "passive"))
      (node (ref "R21") (pin "1") (pinfunction "1_1") (pintype "passive"))
      (node (ref "U1") (pin "5") (pinfunction "FB_5") (pintype "bidirectional"))
    )
    (net (code "79") (name "Net-(U1-SW)") (class "Default")
      (node (ref "L4") (pin "1") (pinfunction "1_1") (pintype "bidirectional"))
      (node (ref "U1") (pin "3") (pinfunction "SW_3") (pintype "bidirectional"))
    )
    (net (code "80") (name "Net-(U5-FB)") (class "Default")
      (node (ref "R1") (pin "2") (pinfunction "2_2") (pintype "passive"))
      (node (ref "R2") (pin "1") (pinfunction "1_1") (pintype "passive"))
      (node (ref "U5") (pin "3") (pinfunction "FB_3") (pintype "bidirectional"))
    )
    (net (code "81") (name "Net-(U6-RXD)") (class "Default")
      (node (ref "R71") (pin "2") (pinfunction "2_2") (pintype "passive"))
      (node (ref "U6") (pin "3") (pinfunction "RXD_3") (pintype "bidirectional"))
    )
    (net (code "82") (name "Net-(U6-TXD)") (class "Default")
      (node (ref "R72") (pin "2") (pinfunction "2_2") (pintype "passive"))
      (node (ref "U6") (pin "2") (pinfunction "TXD_2") (pintype "bidirectional"))
    )
    (net (code "83") (name "Net-(U11-VON)") (class "Default")
      (node (ref "C39") (pin "2") (pinfunction "2_2") (pintype "passive"))
      (node (ref "U11") (pin "5") (pinfunction "VON_5") (pintype "bidirectional"))
    )
    (net (code "84") (name "Net-(U11-VOP)") (class "Default")
      (node (ref "C38") (pin "2") (pinfunction "2_2") (pintype "passive"))
      (node (ref "U11") (pin "8") (pinfunction "VOP_8") (pintype "bidirectional"))
    )
    (net (code "85") (name "unconnected-(J2-GND4-PadP$51)") (class "Default")
      (node (ref "J2") (pin "P$51") (pinfunction "GND4_P$51") (pintype "bidirectional"))
    )
    (net (code "86") (name "unconnected-(J2-GND5-PadP$52)") (class "Default")
      (node (ref "J2") (pin "P$52") (pinfunction "GND5_P$52") (pintype "bidirectional"))
    )
    (net (code "87") (name "unconnected-(J2-NC-PadP$6)") (class "Default")
      (node (ref "J2") (pin "P$6") (pinfunction "NC_P$6") (pintype "bidirectional"))
    )
    (net (code "88") (name "unconnected-(J2-NC1-PadP$2)") (class "Default")
      (node (ref "J2") (pin "P$2") (pinfunction "NC1_P$2") (pintype "bidirectional"))
    )
    (net (code "89") (name "unconnected-(J2-NC2-PadP$1)") (class "Default")
      (node (ref "J2") (pin "P$1") (pinfunction "NC2_P$1") (pintype "bidirectional"))
    )
    (net (code "90") (name "unconnected-(J3-SBU1-PadA8)") (class "Default")
      (node (ref "J3") (pin "A8") (pinfunction "SBU1_A8") (pintype "bidirectional"))
    )
    (net (code "91") (name "unconnected-(J3-SBU2-PadB8)") (class "Default")
      (node (ref "J3") (pin "B8") (pinfunction "SBU2_B8") (pintype "bidirectional"))
    )
    (net (code "92") (name "unconnected-(J4-P$3-Pad3)") (class "Default")
      (node (ref "J4") (pin "3") (pinfunction "P$3_3") (pintype "bidirectional"))
    )
    (net (code "93") (name "unconnected-(J7-Pad2)") (class "Default")
      (node (ref "J7") (pin "2") (pinfunction "2_2") (pintype "bidirectional"))
    )
    (net (code "94") (name "unconnected-(SD1-CDN-Pad9)") (class "Default")
      (node (ref "SD1") (pin "9") (pinfunction "CDN_9") (pintype "bidirectional"))
    )
    (net (code "95") (name "unconnected-(U2-NC1-Pad28)") (class "Default")
      (node (ref "U2") (pin "28") (pinfunction "NC1_28") (pintype "bidirectional"))
    )
    (net (code "96") (name "unconnected-(U2-NC2-Pad29)") (class "Default")
      (node (ref "U2") (pin "29") (pinfunction "NC2_29") (pintype "bidirectional"))
    )
    (net (code "97") (name "unconnected-(U2-NC3-Pad30)") (class "Default")
      (node (ref "U2") (pin "30") (pinfunction "NC3_30") (pintype "bidirectional"))
    )
    (net (code "98") (name "unconnected-(U6-CTS#-Pad9)") (class "Default")
      (node (ref "U6") (pin "9") (pinfunction "CTS#_9") (pintype "bidirectional"))
    )
    (net (code "99") (name "unconnected-(U6-DCD#-Pad12)") (class "Default")
      (node (ref "U6") (pin "12") (pinfunction "DCD#_12") (pintype "bidirectional"))
    )
    (net (code "100") (name "unconnected-(U6-DSR#-Pad10)") (class "Default")
      (node (ref "U6") (pin "10") (pinfunction "DSR#_10") (pintype "bidirectional"))
    )
    (net (code "101") (name "unconnected-(U6-DTR#-Pad13)") (class "Default")
      (node (ref "U6") (pin "13") (pinfunction "DTR#_13") (pintype "bidirectional"))
    )
    (net (code "102") (name "unconnected-(U6-RI#-Pad11)") (class "Default")
      (node (ref "U6") (pin "11") (pinfunction "RI#_11") (pintype "bidirectional"))
    )
    (net (code "103") (name "unconnected-(U6-RS232-Pad15)") (class "Default")
      (node (ref "U6") (pin "15") (pinfunction "RS232_15") (pintype "bidirectional"))
    )
    (net (code "104") (name "unconnected-(U6-RTS#-Pad14)") (class "Default")
      (node (ref "U6") (pin "14") (pinfunction "RTS#_14") (pintype "bidirectional"))
    )
    (net (code "105") (name "unconnected-(U6-XI-Pad7)") (class "Default")
      (node (ref "U6") (pin "7") (pinfunction "XI_7") (pintype "bidirectional"))
    )
    (net (code "106") (name "unconnected-(U6-XO-Pad8)") (class "Default")
      (node (ref "U6") (pin "8") (pinfunction "XO_8") (pintype "bidirectional"))
    )
  )
)
